# master.net
KiCad netlist of a schematic drawn in EAGLE
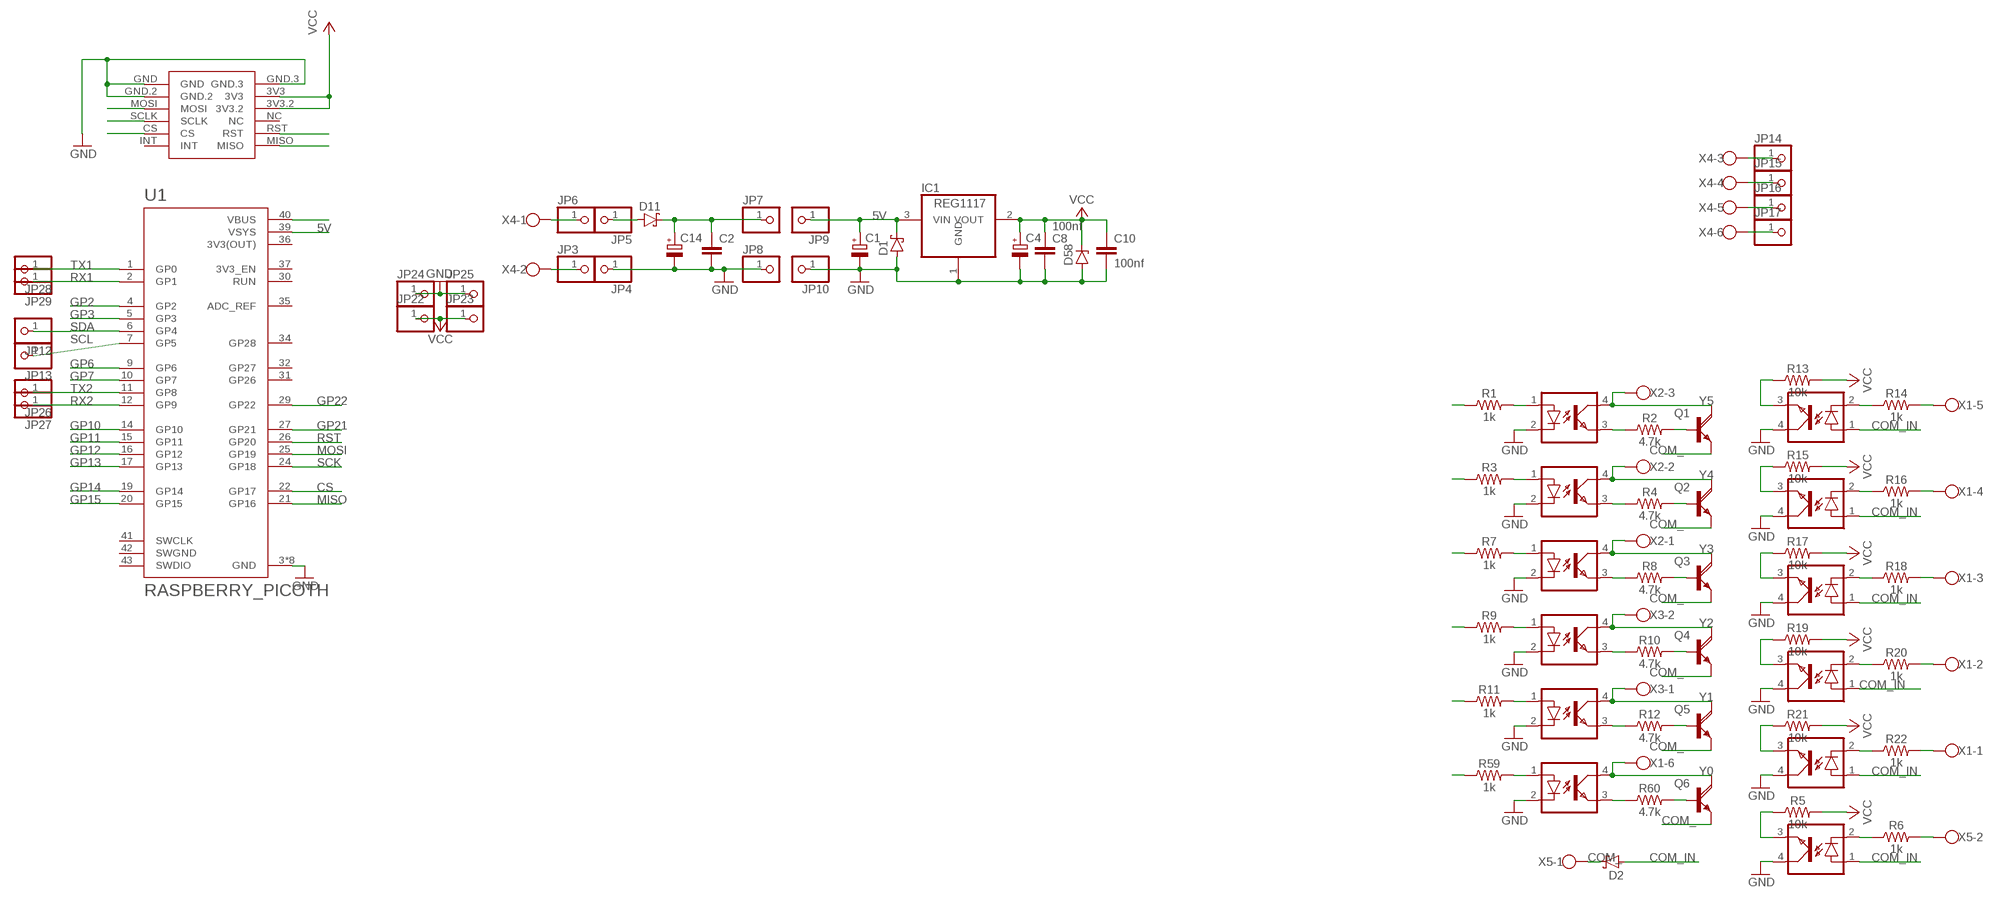
[diagram p0: schematic, sheet 1]

(export (version "E")
  (design (tool "Eeschema 10.0.6"))
  (components
    (comp (ref "C1")
      (value "CPOL-EUE2.5-7")
      (footprint "eagle-import:E2,5-7")
      (libsource (lib "eagle-import") (part "CPOL-EUE2.5-7"))
    )
    (comp (ref "C2")
      (value "C-EUC1206K")
      (footprint "eagle-import:C1206K")
      (libsource (lib "eagle-import") (part "C-EUC1206K"))
    )
    (comp (ref "C4")
      (value "CPOL-EUE2.5-7")
      (footprint "eagle-import:E2,5-7")
      (libsource (lib "eagle-import") (part "CPOL-EUE2.5-7"))
    )
    (comp (ref "C8")
      (value "100nf")
      (footprint "eagle-import:0805")
      (libsource (lib "eagle-import") (part "39NF-0805-50V-10%"))
    )
    (comp (ref "C10")
      (value "100nf")
      (footprint "eagle-import:0805")
      (libsource (lib "eagle-import") (part "39NF-0805-50V-10%"))
    )
    (comp (ref "C14")
      (value "CPOL-EUE2.5-7")
      (footprint "eagle-import:E2,5-7")
      (libsource (lib "eagle-import") (part "CPOL-EUE2.5-7"))
    )
    (comp (ref "D1")
      (value "SCHOTTKY-DIODESMD")
      (footprint "eagle-import:SMB")
      (libsource (lib "eagle-import") (part "SCHOTTKY-DIODESMD"))
    )
    (comp (ref "D2")
      (value "SCHOTTKY-DIODESMD")
      (footprint "eagle-import:SMB")
      (libsource (lib "eagle-import") (part "SCHOTTKY-DIODESMD"))
    )
    (comp (ref "D11")
      (value "SCHOTTKY-DIODESMD")
      (footprint "eagle-import:SMB")
      (libsource (lib "eagle-import") (part "SCHOTTKY-DIODESMD"))
    )
    (comp (ref "D58")
      (value "ZENER-DIODESOD80C")
      (footprint "eagle-import:SOD80C")
      (libsource (lib "eagle-import") (part "ZENER-DIODESOD80C"))
    )
    (comp (ref "IC1")
      (value "REG1117")
      (footprint "eagle-import:SOT223")
      (libsource (lib "eagle-import") (part "REG1117"))
    )
    (comp (ref "JP3")
      (value "PINHD-1X1")
      (footprint "eagle-import:1X01")
      (libsource (lib "eagle-import") (part "PINHD-1X1"))
    )
    (comp (ref "JP4")
      (value "PINHD-1X1")
      (footprint "eagle-import:1X01")
      (libsource (lib "eagle-import") (part "PINHD-1X1"))
    )
    (comp (ref "JP5")
      (value "PINHD-1X1")
      (footprint "eagle-import:1X01")
      (libsource (lib "eagle-import") (part "PINHD-1X1"))
    )
    (comp (ref "JP6")
      (value "PINHD-1X1")
      (footprint "eagle-import:1X01")
      (libsource (lib "eagle-import") (part "PINHD-1X1"))
    )
    (comp (ref "JP7")
      (value "PINHD-1X1")
      (footprint "eagle-import:1X01")
      (libsource (lib "eagle-import") (part "PINHD-1X1"))
    )
    (comp (ref "JP8")
      (value "PINHD-1X1")
      (footprint "eagle-import:1X01")
      (libsource (lib "eagle-import") (part "PINHD-1X1"))
    )
    (comp (ref "JP9")
      (value "PINHD-1X1")
      (footprint "eagle-import:1X01")
      (libsource (lib "eagle-import") (part "PINHD-1X1"))
    )
    (comp (ref "JP10")
      (value "PINHD-1X1")
      (footprint "eagle-import:1X01")
      (libsource (lib "eagle-import") (part "PINHD-1X1"))
    )
    (comp (ref "JP12")
      (value "PINHD-1X1")
      (footprint "eagle-import:1X01")
      (libsource (lib "eagle-import") (part "PINHD-1X1"))
    )
    (comp (ref "JP13")
      (value "PINHD-1X1")
      (footprint "eagle-import:1X01")
      (libsource (lib "eagle-import") (part "PINHD-1X1"))
    )
    (comp (ref "JP14")
      (value "PINHD-1X1")
      (footprint "eagle-import:1X01")
      (libsource (lib "eagle-import") (part "PINHD-1X1"))
    )
    (comp (ref "JP15")
      (value "PINHD-1X1")
      (footprint "eagle-import:1X01")
      (libsource (lib "eagle-import") (part "PINHD-1X1"))
    )
    (comp (ref "JP16")
      (value "PINHD-1X1")
      (footprint "eagle-import:1X01")
      (libsource (lib "eagle-import") (part "PINHD-1X1"))
    )
    (comp (ref "JP17")
      (value "PINHD-1X1")
      (footprint "eagle-import:1X01")
      (libsource (lib "eagle-import") (part "PINHD-1X1"))
    )
    (comp (ref "JP22")
      (value "PINHD-1X1")
      (footprint "eagle-import:1X01")
      (libsource (lib "eagle-import") (part "PINHD-1X1"))
    )
    (comp (ref "JP23")
      (value "PINHD-1X1")
      (footprint "eagle-import:1X01")
      (libsource (lib "eagle-import") (part "PINHD-1X1"))
    )
    (comp (ref "JP24")
      (value "PINHD-1X1")
      (footprint "eagle-import:1X01")
      (libsource (lib "eagle-import") (part "PINHD-1X1"))
    )
    (comp (ref "JP25")
      (value "PINHD-1X1")
      (footprint "eagle-import:1X01")
      (libsource (lib "eagle-import") (part "PINHD-1X1"))
    )
    (comp (ref "JP26")
      (value "PINHD-1X1")
      (footprint "eagle-import:1X01")
      (libsource (lib "eagle-import") (part "PINHD-1X1"))
    )
    (comp (ref "JP27")
      (value "PINHD-1X1")
      (footprint "eagle-import:1X01")
      (libsource (lib "eagle-import") (part "PINHD-1X1"))
    )
    (comp (ref "JP28")
      (value "PINHD-1X1")
      (footprint "eagle-import:1X01")
      (libsource (lib "eagle-import") (part "PINHD-1X1"))
    )
    (comp (ref "JP29")
      (value "PINHD-1X1")
      (footprint "eagle-import:1X01")
      (libsource (lib "eagle-import") (part "PINHD-1X1"))
    )
    (comp (ref "OK1")
      (value "PC817")
      (footprint "eagle-import:DIL04")
      (fields (field (name "MPN") "PC817X4J000F"))
      (libsource (lib "eagle-import") (part "PC817"))
    )
    (comp (ref "OK2")
      (value "PC817")
      (footprint "eagle-import:DIL04")
      (fields (field (name "MPN") "PC817X4J000F"))
      (libsource (lib "eagle-import") (part "PC817"))
    )
    (comp (ref "OK3")
      (value "PC817")
      (footprint "eagle-import:DIL04")
      (fields (field (name "MPN") "PC817X4J000F"))
      (libsource (lib "eagle-import") (part "PC817"))
    )
    (comp (ref "OK4")
      (value "PC817")
      (footprint "eagle-import:DIL04")
      (fields (field (name "MPN") "PC817X4J000F"))
      (libsource (lib "eagle-import") (part "PC817"))
    )
    (comp (ref "OK5")
      (value "PC817")
      (footprint "eagle-import:DIL04")
      (fields (field (name "MPN") "PC817X4J000F"))
      (libsource (lib "eagle-import") (part "PC817"))
    )
    (comp (ref "OK6")
      (value "PC817")
      (footprint "eagle-import:DIL04")
      (fields (field (name "MPN") "PC817X4J000F"))
      (libsource (lib "eagle-import") (part "PC817"))
    )
    (comp (ref "OK7")
      (value "PC817")
      (footprint "eagle-import:DIL04")
      (fields (field (name "MPN") "PC817X4J000F"))
      (libsource (lib "eagle-import") (part "PC817"))
    )
    (comp (ref "OK8")
      (value "PC817")
      (footprint "eagle-import:DIL04")
      (fields (field (name "MPN") "PC817X4J000F"))
      (libsource (lib "eagle-import") (part "PC817"))
    )
    (comp (ref "OK9")
      (value "PC817")
      (footprint "eagle-import:DIL04")
      (fields (field (name "MPN") "PC817X4J000F"))
      (libsource (lib "eagle-import") (part "PC817"))
    )
    (comp (ref "OK10")
      (value "PC817")
      (footprint "eagle-import:DIL04")
      (fields (field (name "MPN") "PC817X4J000F"))
      (libsource (lib "eagle-import") (part "PC817"))
    )
    (comp (ref "OK11")
      (value "PC817")
      (footprint "eagle-import:DIL04")
      (fields (field (name "MPN") "PC817X4J000F"))
      (libsource (lib "eagle-import") (part "PC817"))
    )
    (comp (ref "OK14")
      (value "PC817")
      (footprint "eagle-import:DIL04")
      (fields (field (name "MPN") "PC817X4J000F"))
      (libsource (lib "eagle-import") (part "PC817"))
    )
    (comp (ref "Q1")
      (value "TIP120V")
      (footprint "eagle-import:TO220AV")
      (libsource (lib "eagle-import") (part "TIP120V"))
    )
    (comp (ref "Q2")
      (value "TIP120V")
      (footprint "eagle-import:TO220AV")
      (libsource (lib "eagle-import") (part "TIP120V"))
    )
    (comp (ref "Q3")
      (value "TIP120V")
      (footprint "eagle-import:TO220AV")
      (libsource (lib "eagle-import") (part "TIP120V"))
    )
    (comp (ref "Q4")
      (value "TIP120V")
      (footprint "eagle-import:TO220AV")
      (libsource (lib "eagle-import") (part "TIP120V"))
    )
    (comp (ref "Q5")
      (value "TIP120V")
      (footprint "eagle-import:TO220AV")
      (libsource (lib "eagle-import") (part "TIP120V"))
    )
    (comp (ref "Q6")
      (value "TIP120V")
      (footprint "eagle-import:TO220AV")
      (libsource (lib "eagle-import") (part "TIP120V"))
    )
    (comp (ref "R1")
      (value "1k")
      (footprint "eagle-import:0805")
      (libsource (lib "eagle-import") (part "0.75OHM-0805-1/4W-1%"))
    )
    (comp (ref "R2")
      (value "4.7k")
      (footprint "eagle-import:0805")
      (libsource (lib "eagle-import") (part "0.75OHM-0805-1/4W-1%"))
    )
    (comp (ref "R3")
      (value "1k")
      (footprint "eagle-import:0805")
      (libsource (lib "eagle-import") (part "0.75OHM-0805-1/4W-1%"))
    )
    (comp (ref "R4")
      (value "4.7k")
      (footprint "eagle-import:0805")
      (libsource (lib "eagle-import") (part "0.75OHM-0805-1/4W-1%"))
    )
    (comp (ref "R5")
      (value "10k")
      (footprint "eagle-import:0805")
      (libsource (lib "eagle-import") (part "0.75OHM-0805-1/4W-1%"))
    )
    (comp (ref "R6")
      (value "1k")
      (footprint "eagle-import:0805")
      (libsource (lib "eagle-import") (part "0.75OHM-0805-1/4W-1%"))
    )
    (comp (ref "R7")
      (value "1k")
      (footprint "eagle-import:0805")
      (libsource (lib "eagle-import") (part "0.75OHM-0805-1/4W-1%"))
    )
    (comp (ref "R8")
      (value "4.7k")
      (footprint "eagle-import:0805")
      (libsource (lib "eagle-import") (part "0.75OHM-0805-1/4W-1%"))
    )
    (comp (ref "R9")
      (value "1k")
      (footprint "eagle-import:0805")
      (libsource (lib "eagle-import") (part "0.75OHM-0805-1/4W-1%"))
    )
    (comp (ref "R10")
      (value "4.7k")
      (footprint "eagle-import:0805")
      (libsource (lib "eagle-import") (part "0.75OHM-0805-1/4W-1%"))
    )
    (comp (ref "R11")
      (value "1k")
      (footprint "eagle-import:0805")
      (libsource (lib "eagle-import") (part "0.75OHM-0805-1/4W-1%"))
    )
    (comp (ref "R12")
      (value "4.7k")
      (footprint "eagle-import:0805")
      (libsource (lib "eagle-import") (part "0.75OHM-0805-1/4W-1%"))
    )
    (comp (ref "R13")
      (value "10k")
      (footprint "eagle-import:0805")
      (libsource (lib "eagle-import") (part "0.75OHM-0805-1/4W-1%"))
    )
    (comp (ref "R14")
      (value "1k")
      (footprint "eagle-import:0805")
      (libsource (lib "eagle-import") (part "0.75OHM-0805-1/4W-1%"))
    )
    (comp (ref "R15")
      (value "10k")
      (footprint "eagle-import:0805")
      (libsource (lib "eagle-import") (part "0.75OHM-0805-1/4W-1%"))
    )
    (comp (ref "R16")
      (value "1k")
      (footprint "eagle-import:0805")
      (libsource (lib "eagle-import") (part "0.75OHM-0805-1/4W-1%"))
    )
    (comp (ref "R17")
      (value "10k")
      (footprint "eagle-import:0805")
      (libsource (lib "eagle-import") (part "0.75OHM-0805-1/4W-1%"))
    )
    (comp (ref "R18")
      (value "1k")
      (footprint "eagle-import:0805")
      (libsource (lib "eagle-import") (part "0.75OHM-0805-1/4W-1%"))
    )
    (comp (ref "R19")
      (value "10k")
      (footprint "eagle-import:0805")
      (libsource (lib "eagle-import") (part "0.75OHM-0805-1/4W-1%"))
    )
    (comp (ref "R20")
      (value "1k")
      (footprint "eagle-import:0805")
      (libsource (lib "eagle-import") (part "0.75OHM-0805-1/4W-1%"))
    )
    (comp (ref "R21")
      (value "10k")
      (footprint "eagle-import:0805")
      (libsource (lib "eagle-import") (part "0.75OHM-0805-1/4W-1%"))
    )
    (comp (ref "R22")
      (value "1k")
      (footprint "eagle-import:0805")
      (libsource (lib "eagle-import") (part "0.75OHM-0805-1/4W-1%"))
    )
    (comp (ref "R59")
      (value "1k")
      (footprint "eagle-import:0805")
      (libsource (lib "eagle-import") (part "0.75OHM-0805-1/4W-1%"))
    )
    (comp (ref "R60")
      (value "4.7k")
      (footprint "eagle-import:0805")
      (libsource (lib "eagle-import") (part "0.75OHM-0805-1/4W-1%"))
    )
    (comp (ref "U$2")
      (value "MINI_W5500")
      (footprint "eagle-import:MINI_W5500")
      (libsource (lib "eagle-import") (part "MINI_W5500"))
    )
    (comp (ref "U1")
      (value "RASPBERRY_PICOTH")
      (footprint "eagle-import:PICO-PKG-TH")
      (libsource (lib "eagle-import") (part "RASPBERRY_PICOTH"))
    )
    (comp (ref "X1")
      (value "W237-136")
      (footprint "eagle-import:W237-136")
      (fields (field (name "MPN") "237-136"))
      (libsource (lib "eagle-import") (part "W237-136"))
    )
    (comp (ref "X2")
      (value "W237-103")
      (footprint "eagle-import:W237-103")
      (fields (field (name "MPN") "237-103"))
      (libsource (lib "eagle-import") (part "W237-103"))
    )
    (comp (ref "X3")
      (value "W237-102")
      (footprint "eagle-import:W237-102")
      (fields (field (name "MPN") "237-102"))
      (libsource (lib "eagle-import") (part "W237-102"))
    )
    (comp (ref "X4")
      (value "W237-136")
      (footprint "eagle-import:W237-136")
      (fields (field (name "MPN") "237-136"))
      (libsource (lib "eagle-import") (part "W237-136"))
    )
    (comp (ref "X5")
      (value "W237-102")
      (footprint "eagle-import:W237-102")
      (fields (field (name "MPN") "237-102"))
      (libsource (lib "eagle-import") (part "W237-102"))
    )
  )
  (nets
    (net (code "1") (name "/3V3(OUT)") (class "Default")
      (node (ref "U1") (pin "36") (pinfunction "3V3(OUT)_36") (pintype "power_in"))
    )
    (net (code "2") (name "/5V") (class "Default")
      (node (ref "C1") (pin "+") (pinfunction "+_+") (pintype "passive"))
      (node (ref "D1") (pin "C") (pinfunction "C_C") (pintype "passive"))
      (node (ref "IC1") (pin "3") (pinfunction "VIN_3") (pintype "input"))
      (node (ref "JP9") (pin "1") (pinfunction "1_1") (pintype "passive"))
      (node (ref "U1") (pin "39") (pinfunction "VSYS_39") (pintype "power_in"))
    )
    (net (code "3") (name "/COM_") (class "Default")
      (node (ref "D2") (pin "C") (pinfunction "C_C") (pintype "passive"))
      (node (ref "Q1") (pin "E") (pinfunction "E_E") (pintype "passive"))
      (node (ref "Q2") (pin "E") (pinfunction "E_E") (pintype "passive"))
      (node (ref "Q3") (pin "E") (pinfunction "E_E") (pintype "passive"))
      (node (ref "Q4") (pin "E") (pinfunction "E_E") (pintype "passive"))
      (node (ref "Q5") (pin "E") (pinfunction "E_E") (pintype "passive"))
      (node (ref "Q6") (pin "E") (pinfunction "E_E") (pintype "passive"))
      (node (ref "X5") (pin "1") (pinfunction "KL_1") (pintype "passive"))
    )
    (net (code "4") (name "/COM_IN") (class "Default")
      (node (ref "D2") (pin "A") (pinfunction "A_A") (pintype "passive"))
      (node (ref "OK10") (pin "1") (pinfunction "A_1") (pintype "passive"))
      (node (ref "OK11") (pin "1") (pinfunction "A_1") (pintype "passive"))
      (node (ref "OK3") (pin "1") (pinfunction "A_1") (pintype "passive"))
      (node (ref "OK7") (pin "1") (pinfunction "A_1") (pintype "passive"))
      (node (ref "OK8") (pin "1") (pinfunction "A_1") (pintype "passive"))
      (node (ref "OK9") (pin "1") (pinfunction "A_1") (pintype "passive"))
    )
    (net (code "5") (name "/CS") (class "Default")
      (node (ref "U1") (pin "22") (pinfunction "GP17_22") (pintype "bidirectional"))
    )
    (net (code "6") (name "/GP2") (class "Default")
      (node (ref "U1") (pin "4") (pinfunction "GP2_4") (pintype "bidirectional"))
    )
    (net (code "7") (name "/GP3") (class "Default")
      (node (ref "U1") (pin "5") (pinfunction "GP3_5") (pintype "bidirectional"))
    )
    (net (code "8") (name "/GP6") (class "Default")
      (node (ref "U1") (pin "9") (pinfunction "GP6_9") (pintype "bidirectional"))
    )
    (net (code "9") (name "/GP7") (class "Default")
      (node (ref "U1") (pin "10") (pinfunction "GP7_10") (pintype "bidirectional"))
    )
    (net (code "10") (name "/GP10") (class "Default")
      (node (ref "U1") (pin "14") (pinfunction "GP10_14") (pintype "bidirectional"))
    )
    (net (code "11") (name "/GP11") (class "Default")
      (node (ref "U1") (pin "15") (pinfunction "GP11_15") (pintype "bidirectional"))
    )
    (net (code "12") (name "/GP12") (class "Default")
      (node (ref "U1") (pin "16") (pinfunction "GP12_16") (pintype "bidirectional"))
    )
    (net (code "13") (name "/GP13") (class "Default")
      (node (ref "U1") (pin "17") (pinfunction "GP13_17") (pintype "bidirectional"))
    )
    (net (code "14") (name "/GP14") (class "Default")
      (node (ref "U1") (pin "19") (pinfunction "GP14_19") (pintype "bidirectional"))
    )
    (net (code "15") (name "/GP15") (class "Default")
      (node (ref "U1") (pin "20") (pinfunction "GP15_20") (pintype "bidirectional"))
    )
    (net (code "16") (name "/GP21") (class "Default")
      (node (ref "U1") (pin "27") (pinfunction "GP21_27") (pintype "bidirectional"))
    )
    (net (code "17") (name "/GP22") (class "Default")
      (node (ref "U1") (pin "29") (pinfunction "GP22_29") (pintype "bidirectional"))
    )
    (net (code "18") (name "/MISO") (class "Default")
      (node (ref "U1") (pin "21") (pinfunction "GP16_21") (pintype "bidirectional"))
    )
    (net (code "19") (name "/MOSI") (class "Default")
      (node (ref "U1") (pin "25") (pinfunction "GP19_25") (pintype "bidirectional"))
    )
    (net (code "20") (name "/RST") (class "Default")
      (node (ref "U1") (pin "26") (pinfunction "GP20_26") (pintype "bidirectional"))
    )
    (net (code "21") (name "/RX1") (class "Default")
      (node (ref "JP29") (pin "1") (pinfunction "1_1") (pintype "passive"))
      (node (ref "U1") (pin "2") (pinfunction "GP1_2") (pintype "bidirectional"))
    )
    (net (code "22") (name "/RX2") (class "Default")
      (node (ref "JP27") (pin "1") (pinfunction "1_1") (pintype "passive"))
      (node (ref "U1") (pin "12") (pinfunction "GP9_12") (pintype "bidirectional"))
    )
    (net (code "23") (name "/SCK") (class "Default")
      (node (ref "U1") (pin "24") (pinfunction "GP18_24") (pintype "bidirectional"))
    )
    (net (code "24") (name "/SCL") (class "Default")
      (node (ref "JP13") (pin "1") (pinfunction "1_1") (pintype "passive"))
      (node (ref "U1") (pin "7") (pinfunction "GP5_7") (pintype "bidirectional"))
    )
    (net (code "25") (name "/SDA") (class "Default")
      (node (ref "JP12") (pin "1") (pinfunction "1_1") (pintype "passive"))
      (node (ref "U1") (pin "6") (pinfunction "GP4_6") (pintype "bidirectional"))
    )
    (net (code "26") (name "/SWGND") (class "Default")
      (node (ref "U1") (pin "42") (pinfunction "SWGND_42") (pintype "power_in"))
    )
    (net (code "27") (name "/TX1") (class "Default")
      (node (ref "JP28") (pin "1") (pinfunction "1_1") (pintype "passive"))
      (node (ref "U1") (pin "1") (pinfunction "GP0_1") (pintype "bidirectional"))
    )
    (net (code "28") (name "/TX2") (class "Default")
      (node (ref "JP26") (pin "1") (pinfunction "1_1") (pintype "passive"))
      (node (ref "U1") (pin "11") (pinfunction "GP8_11") (pintype "bidirectional"))
    )
    (net (code "29") (name "/Y0") (class "Default")
      (node (ref "OK14") (pin "4") (pinfunction "COL_4") (pintype "passive"))
      (node (ref "Q6") (pin "C") (pinfunction "C_C") (pintype "passive"))
      (node (ref "X1") (pin "6") (pinfunction "KL_6") (pintype "passive"))
    )
    (net (code "30") (name "/Y1") (class "Default")
      (node (ref "OK6") (pin "4") (pinfunction "COL_4") (pintype "passive"))
      (node (ref "Q5") (pin "C") (pinfunction "C_C") (pintype "passive"))
      (node (ref "X3") (pin "1") (pinfunction "KL_1") (pintype "passive"))
    )
    (net (code "31") (name "/Y2") (class "Default")
      (node (ref "OK5") (pin "4") (pinfunction "COL_4") (pintype "passive"))
      (node (ref "Q4") (pin "C") (pinfunction "C_C") (pintype "passive"))
      (node (ref "X3") (pin "2") (pinfunction "KL_2") (pintype "passive"))
    )
    (net (code "32") (name "/Y3") (class "Default")
      (node (ref "OK4") (pin "4") (pinfunction "COL_4") (pintype "passive"))
      (node (ref "Q3") (pin "C") (pinfunction "C_C") (pintype "passive"))
      (node (ref "X2") (pin "1") (pinfunction "KL_1") (pintype "passive"))
    )
    (net (code "33") (name "/Y4") (class "Default")
      (node (ref "OK2") (pin "4") (pinfunction "COL_4") (pintype "passive"))
      (node (ref "Q2") (pin "C") (pinfunction "C_C") (pintype "passive"))
      (node (ref "X2") (pin "2") (pinfunction "KL_2") (pintype "passive"))
    )
    (net (code "34") (name "/Y5") (class "Default")
      (node (ref "OK1") (pin "4") (pinfunction "COL_4") (pintype "passive"))
      (node (ref "Q1") (pin "C") (pinfunction "C_C") (pintype "passive"))
      (node (ref "X2") (pin "3") (pinfunction "KL_3") (pintype "passive"))
    )
    (net (code "35") (name "GND") (class "Default")
      (node (ref "C1") (pin "-") (pinfunction "-_-") (pintype "passive"))
      (node (ref "C10") (pin "2") (pinfunction "2_2") (pintype "passive"))
      (node (ref "C14") (pin "-") (pinfunction "-_-") (pintype "passive"))
      (node (ref "C2") (pin "2") (pinfunction "2_2") (pintype "passive"))
      (node (ref "C4") (pin "-") (pinfunction "-_-") (pintype "passive"))
      (node (ref "C8") (pin "2") (pinfunction "2_2") (pintype "passive"))
      (node (ref "D1") (pin "A") (pinfunction "A_A") (pintype "passive"))
      (node (ref "D58") (pin "A") (pinfunction "A_A") (pintype "passive"))
      (node (ref "IC1") (pin "1") (pinfunction "GND_1") (pintype "power_in"))
      (node (ref "JP10") (pin "1") (pinfunction "1_1") (pintype "passive"))
      (node (ref "JP24") (pin "1") (pinfunction "1_1") (pintype "passive"))
      (node (ref "JP25") (pin "1") (pinfunction "1_1") (pintype "passive"))
      (node (ref "JP4") (pin "1") (pinfunction "1_1") (pintype "passive"))
      (node (ref "JP8") (pin "1") (pinfunction "1_1") (pintype "passive"))
      (node (ref "OK1") (pin "2") (pinfunction "C_2") (pintype "passive"))
      (node (ref "OK10") (pin "4") (pinfunction "COL_4") (pintype "passive"))
      (node (ref "OK11") (pin "4") (pinfunction "COL_4") (pintype "passive"))
      (node (ref "OK14") (pin "2") (pinfunction "C_2") (pintype "passive"))
      (node (ref "OK2") (pin "2") (pinfunction "C_2") (pintype "passive"))
      (node (ref "OK3") (pin "4") (pinfunction "COL_4") (pintype "passive"))
      (node (ref "OK4") (pin "2") (pinfunction "C_2") (pintype "passive"))
      (node (ref "OK5") (pin "2") (pinfunction "C_2") (pintype "passive"))
      (node (ref "OK6") (pin "2") (pinfunction "C_2") (pintype "passive"))
      (node (ref "OK7") (pin "4") (pinfunction "COL_4") (pintype "passive"))
      (node (ref "OK8") (pin "4") (pinfunction "COL_4") (pintype "passive"))
      (node (ref "OK9") (pin "4") (pinfunction "COL_4") (pintype "passive"))
      (node (ref "U$2") (pin "GND") (pinfunction "GND_GND") (pintype "bidirectional"))
      (node (ref "U$2") (pin "GND.2") (pinfunction "GND.2_GND.2") (pintype "bidirectional"))
      (node (ref "U$2") (pin "GND.3") (pinfunction "GND.3_GND.3") (pintype "bidirectional"))
      (node (ref "U1") (pin "13") (pinfunction "GND_13") (pintype "power_in"))
      (node (ref "U1") (pin "18") (pinfunction "GND_18") (pintype "power_in"))
      (node (ref "U1") (pin "23") (pinfunction "GND_23") (pintype "power_in"))
      (node (ref "U1") (pin "28") (pinfunction "GND_28") (pintype "power_in"))
      (node (ref "U1") (pin "3") (pinfunction "GND_3") (pintype "power_in"))
      (node (ref "U1") (pin "33") (pinfunction "GND_33") (pintype "power_in"))
      (node (ref "U1") (pin "38") (pinfunction "GND_38") (pintype "power_in"))
      (node (ref "U1") (pin "8") (pinfunction "GND_8") (pintype "power_in"))
    )
    (net (code "36") (name "Net-(C14-Pad+)") (class "Default")
      (node (ref "C14") (pin "+") (pinfunction "+_+") (pintype "passive"))
      (node (ref "C2") (pin "1") (pinfunction "1_1") (pintype "passive"))
      (node (ref "D11") (pin "C") (pinfunction "C_C") (pintype "passive"))
      (node (ref "JP7") (pin "1") (pinfunction "1_1") (pintype "passive"))
    )
    (net (code "37") (name "Net-(D11-PadA)") (class "Default")
      (node (ref "D11") (pin "A") (pinfunction "A_A") (pintype "passive"))
      (node (ref "JP5") (pin "1") (pinfunction "1_1") (pintype "passive"))
    )
    (net (code "38") (name "Net-(OK1-A)") (class "Default")
      (node (ref "OK1") (pin "1") (pinfunction "A_1") (pintype "passive"))
      (node (ref "R1") (pin "2") (pinfunction "2_2") (pintype "passive"))
    )
    (net (code "39") (name "Net-(OK1-EMIT)") (class "Default")
      (node (ref "OK1") (pin "3") (pinfunction "EMIT_3") (pintype "passive"))
      (node (ref "R2") (pin "1") (pinfunction "1_1") (pintype "passive"))
    )
    (net (code "40") (name "Net-(OK2-A)") (class "Default")
      (node (ref "OK2") (pin "1") (pinfunction "A_1") (pintype "passive"))
      (node (ref "R3") (pin "2") (pinfunction "2_2") (pintype "passive"))
    )
    (net (code "41") (name "Net-(OK2-EMIT)") (class "Default")
      (node (ref "OK2") (pin "3") (pinfunction "EMIT_3") (pintype "passive"))
      (node (ref "R4") (pin "1") (pinfunction "1_1") (pintype "passive"))
    )
    (net (code "42") (name "Net-(OK3-C)") (class "Default")
      (node (ref "OK3") (pin "2") (pinfunction "C_2") (pintype "passive"))
      (node (ref "R6") (pin "1") (pinfunction "1_1") (pintype "passive"))
    )
    (net (code "43") (name "Net-(OK3-EMIT)") (class "Default")
      (node (ref "OK3") (pin "3") (pinfunction "EMIT_3") (pintype "passive"))
      (node (ref "R5") (pin "1") (pinfunction "1_1") (pintype "passive"))
    )
    (net (code "44") (name "Net-(OK4-A)") (class "Default")
      (node (ref "OK4") (pin "1") (pinfunction "A_1") (pintype "passive"))
      (node (ref "R7") (pin "2") (pinfunction "2_2") (pintype "passive"))
    )
    (net (code "45") (name "Net-(OK4-EMIT)") (class "Default")
      (node (ref "OK4") (pin "3") (pinfunction "EMIT_3") (pintype "passive"))
      (node (ref "R8") (pin "1") (pinfunction "1_1") (pintype "passive"))
    )
    (net (code "46") (name "Net-(OK5-A)") (class "Default")
      (node (ref "OK5") (pin "1") (pinfunction "A_1") (pintype "passive"))
      (node (ref "R9") (pin "2") (pinfunction "2_2") (pintype "passive"))
    )
    (net (code "47") (name "Net-(OK5-EMIT)") (class "Default")
      (node (ref "OK5") (pin "3") (pinfunction "EMIT_3") (pintype "passive"))
      (node (ref "R10") (pin "1") (pinfunction "1_1") (pintype "passive"))
    )
    (net (code "48") (name "Net-(OK6-A)") (class "Default")
      (node (ref "OK6") (pin "1") (pinfunction "A_1") (pintype "passive"))
      (node (ref "R11") (pin "2") (pinfunction "2_2") (pintype "passive"))
    )
    (net (code "49") (name "Net-(OK6-EMIT)") (class "Default")
      (node (ref "OK6") (pin "3") (pinfunction "EMIT_3") (pintype "passive"))
      (node (ref "R12") (pin "1") (pinfunction "1_1") (pintype "passive"))
    )
    (net (code "50") (name "Net-(OK7-C)") (class "Default")
      (node (ref "OK7") (pin "2") (pinfunction "C_2") (pintype "passive"))
      (node (ref "R14") (pin "1") (pinfunction "1_1") (pintype "passive"))
    )
    (net (code "51") (name "Net-(OK7-EMIT)") (class "Default")
      (node (ref "OK7") (pin "3") (pinfunction "EMIT_3") (pintype "passive"))
      (node (ref "R13") (pin "1") (pinfunction "1_1") (pintype "passive"))
    )
    (net (code "52") (name "Net-(OK8-C)") (class "Default")
      (node (ref "OK8") (pin "2") (pinfunction "C_2") (pintype "passive"))
      (node (ref "R16") (pin "1") (pinfunction "1_1") (pintype "passive"))
    )
    (net (code "53") (name "Net-(OK8-EMIT)") (class "Default")
      (node (ref "OK8") (pin "3") (pinfunction "EMIT_3") (pintype "passive"))
      (node (ref "R15") (pin "1") (pinfunction "1_1") (pintype "passive"))
    )
    (net (code "54") (name "Net-(OK9-C)") (class "Default")
      (node (ref "OK9") (pin "2") (pinfunction "C_2") (pintype "passive"))
      (node (ref "R18") (pin "1") (pinfunction "1_1") (pintype "passive"))
    )
    (net (code "55") (name "Net-(OK9-EMIT)") (class "Default")
      (node (ref "OK9") (pin "3") (pinfunction "EMIT_3") (pintype "passive"))
      (node (ref "R17") (pin "1") (pinfunction "1_1") (pintype "passive"))
    )
    (net (code "56") (name "Net-(OK10-C)") (class "Default")
      (node (ref "OK10") (pin "2") (pinfunction "C_2") (pintype "passive"))
      (node (ref "R20") (pin "1") (pinfunction "1_1") (pintype "passive"))
    )
    (net (code "57") (name "Net-(OK10-EMIT)") (class "Default")
      (node (ref "OK10") (pin "3") (pinfunction "EMIT_3") (pintype "passive"))
      (node (ref "R19") (pin "1") (pinfunction "1_1") (pintype "passive"))
    )
    (net (code "58") (name "Net-(OK11-C)") (class "Default")
      (node (ref "OK11") (pin "2") (pinfunction "C_2") (pintype "passive"))
      (node (ref "R22") (pin "1") (pinfunction "1_1") (pintype "passive"))
    )
    (net (code "59") (name "Net-(OK11-EMIT)") (class "Default")
      (node (ref "OK11") (pin "3") (pinfunction "EMIT_3") (pintype "passive"))
      (node (ref "R21") (pin "1") (pinfunction "1_1") (pintype "passive"))
    )
    (net (code "60") (name "Net-(OK14-A)") (class "Default")
      (node (ref "OK14") (pin "1") (pinfunction "A_1") (pintype "passive"))
      (node (ref "R59") (pin "2") (pinfunction "2_2") (pintype "passive"))
    )
    (net (code "61") (name "Net-(OK14-EMIT)") (class "Default")
      (node (ref "OK14") (pin "3") (pinfunction "EMIT_3") (pintype "passive"))
      (node (ref "R60") (pin "1") (pinfunction "1_1") (pintype "passive"))
    )
    (net (code "62") (name "Net-(Q1-PadB)") (class "Default")
      (node (ref "Q1") (pin "B") (pinfunction "B_B") (pintype "passive"))
      (node (ref "R2") (pin "2") (pinfunction "2_2") (pintype "passive"))
    )
    (net (code "63") (name "Net-(Q2-PadB)") (class "Default")
      (node (ref "Q2") (pin "B") (pinfunction "B_B") (pintype "passive"))
      (node (ref "R4") (pin "2") (pinfunction "2_2") (pintype "passive"))
    )
    (net (code "64") (name "Net-(Q3-PadB)") (class "Default")
      (node (ref "Q3") (pin "B") (pinfunction "B_B") (pintype "passive"))
      (node (ref "R8") (pin "2") (pinfunction "2_2") (pintype "passive"))
    )
    (net (code "65") (name "Net-(Q4-PadB)") (class "Default")
      (node (ref "Q4") (pin "B") (pinfunction "B_B") (pintype "passive"))
      (node (ref "R10") (pin "2") (pinfunction "2_2") (pintype "passive"))
    )
    (net (code "66") (name "Net-(Q5-PadB)") (class "Default")
      (node (ref "Q5") (pin "B") (pinfunction "B_B") (pintype "passive"))
      (node (ref "R12") (pin "2") (pinfunction "2_2") (pintype "passive"))
    )
    (net (code "67") (name "Net-(Q6-PadB)") (class "Default")
      (node (ref "Q6") (pin "B") (pinfunction "B_B") (pintype "passive"))
      (node (ref "R60") (pin "2") (pinfunction "2_2") (pintype "passive"))
    )
    (net (code "68") (name "Net-(X1A-KL)") (class "Default")
      (node (ref "R22") (pin "2") (pinfunction "2_2") (pintype "passive"))
      (node (ref "X1") (pin "1") (pinfunction "KL_1") (pintype "passive"))
    )
    (net (code "69") (name "Net-(X1B-KL)") (class "Default")
      (node (ref "R20") (pin "2") (pinfunction "2_2") (pintype "passive"))
      (node (ref "X1") (pin "2") (pinfunction "KL_2") (pintype "passive"))
    )
    (net (code "70") (name "Net-(X1C-KL)") (class "Default")
      (node (ref "R18") (pin "2") (pinfunction "2_2") (pintype "passive"))
      (node (ref "X1") (pin "3") (pinfunction "KL_3") (pintype "passive"))
    )
    (net (code "71") (name "Net-(X1D-KL)") (class "Default")
      (node (ref "R16") (pin "2") (pinfunction "2_2") (pintype "passive"))
      (node (ref "X1") (pin "4") (pinfunction "KL_4") (pintype "passive"))
    )
    (net (code "72") (name "Net-(X1E-KL)") (class "Default")
      (node (ref "R14") (pin "2") (pinfunction "2_2") (pintype "passive"))
      (node (ref "X1") (pin "5") (pinfunction "KL_5") (pintype "passive"))
    )
    (net (code "73") (name "Net-(X4A-KL)") (class "Default")
      (node (ref "JP6") (pin "1") (pinfunction "1_1") (pintype "passive"))
      (node (ref "X4") (pin "1") (pinfunction "KL_1") (pintype "passive"))
    )
    (net (code "74") (name "Net-(X4B-KL)") (class "Default")
      (node (ref "JP3") (pin "1") (pinfunction "1_1") (pintype "passive"))
      (node (ref "X4") (pin "2") (pinfunction "KL_2") (pintype "passive"))
    )
    (net (code "75") (name "Net-(X4C-KL)") (class "Default")
      (node (ref "JP14") (pin "1") (pinfunction "1_1") (pintype "passive"))
      (node (ref "X4") (pin "3") (pinfunction "KL_3") (pintype "passive"))
    )
    (net (code "76") (name "Net-(X4D-KL)") (class "Default")
      (node (ref "JP15") (pin "1") (pinfunction "1_1") (pintype "passive"))
      (node (ref "X4") (pin "4") (pinfunction "KL_4") (pintype "passive"))
    )
    (net (code "77") (name "Net-(X4E-KL)") (class "Default")
      (node (ref "JP16") (pin "1") (pinfunction "1_1") (pintype "passive"))
      (node (ref "X4") (pin "5") (pinfunction "KL_5") (pintype "passive"))
    )
    (net (code "78") (name "Net-(X4F-KL)") (class "Default")
      (node (ref "JP17") (pin "1") (pinfunction "1_1") (pintype "passive"))
      (node (ref "X4") (pin "6") (pinfunction "KL_6") (pintype "passive"))
    )
    (net (code "79") (name "Net-(X5B-KL)") (class "Default")
      (node (ref "R6") (pin "2") (pinfunction "2_2") (pintype "passive"))
      (node (ref "X5") (pin "2") (pinfunction "KL_2") (pintype "passive"))
    )
    (net (code "80") (name "VCC") (class "Default")
      (node (ref "C10") (pin "1") (pinfunction "1_1") (pintype "passive"))
      (node (ref "C4") (pin "+") (pinfunction "+_+") (pintype "passive"))
      (node (ref "C8") (pin "1") (pinfunction "1_1") (pintype "passive"))
      (node (ref "D58") (pin "C") (pinfunction "C_C") (pintype "passive"))
      (node (ref "IC1") (pin "2") (pinfunction "VOUT_2") (pintype "output"))
      (node (ref "JP22") (pin "1") (pinfunction "1_1") (pintype "passive"))
      (node (ref "JP23") (pin "1") (pinfunction "1_1") (pintype "passive"))
      (node (ref "R13") (pin "2") (pinfunction "2_2") (pintype "passive"))
      (node (ref "R15") (pin "2") (pinfunction "2_2") (pintype "passive"))
      (node (ref "R17") (pin "2") (pinfunction "2_2") (pintype "passive"))
      (node (ref "R19") (pin "2") (pinfunction "2_2") (pintype "passive"))
      (node (ref "R21") (pin "2") (pinfunction "2_2") (pintype "passive"))
      (node (ref "R5") (pin "2") (pinfunction "2_2") (pintype "passive"))
      (node (ref "U$2") (pin "3V3") (pinfunction "3V3_3V3") (pintype "bidirectional"))
      (node (ref "U$2") (pin "3V3.2") (pinfunction "3V3.2_3V3.2") (pintype "bidirectional"))
    )
    (net (code "81") (name "unconnected-(R1-Pad1)") (class "Default")
      (node (ref "R1") (pin "1") (pinfunction "1_1") (pintype "passive"))
    )
    (net (code "82") (name "unconnected-(R3-Pad1)") (class "Default")
      (node (ref "R3") (pin "1") (pinfunction "1_1") (pintype "passive"))
    )
    (net (code "83") (name "unconnected-(R7-Pad1)") (class "Default")
      (node (ref "R7") (pin "1") (pinfunction "1_1") (pintype "passive"))
    )
    (net (code "84") (name "unconnected-(R9-Pad1)") (class "Default")
      (node (ref "R9") (pin "1") (pinfunction "1_1") (pintype "passive"))
    )
    (net (code "85") (name "unconnected-(R11-Pad1)") (class "Default")
      (node (ref "R11") (pin "1") (pinfunction "1_1") (pintype "passive"))
    )
    (net (code "86") (name "unconnected-(R59-Pad1)") (class "Default")
      (node (ref "R59") (pin "1") (pinfunction "1_1") (pintype "passive"))
    )
    (net (code "87") (name "unconnected-(U$2-PadCS)") (class "Default")
      (node (ref "U$2") (pin "CS") (pinfunction "CS_CS") (pintype "bidirectional"))
    )
    (net (code "88") (name "unconnected-(U$2-PadINT)") (class "Default")
      (node (ref "U$2") (pin "INT") (pinfunction "INT_INT") (pintype "bidirectional"))
    )
    (net (code "89") (name "unconnected-(U$2-PadMISO)") (class "Default")
      (node (ref "U$2") (pin "MISO") (pinfunction "MISO_MISO") (pintype "bidirectional"))
    )
    (net (code "90") (name "unconnected-(U$2-PadMOSI)") (class "Default")
      (node (ref "U$2") (pin "MOSI") (pinfunction "MOSI_MOSI") (pintype "bidirectional"))
    )
    (net (code "91") (name "unconnected-(U$2-PadNC)") (class "Default")
      (node (ref "U$2") (pin "NC") (pinfunction "NC_NC") (pintype "bidirectional"))
    )
    (net (code "92") (name "unconnected-(U$2-PadRST)") (class "Default")
      (node (ref "U$2") (pin "RST") (pinfunction "RST_RST") (pintype "bidirectional"))
    )
    (net (code "93") (name "unconnected-(U$2-PadSCLK)") (class "Default")
      (node (ref "U$2") (pin "SCLK") (pinfunction "SCLK_SCLK") (pintype "bidirectional"))
    )
    (net (code "94") (name "unconnected-(U1-3V3_EN-Pad37)") (class "Default")
      (node (ref "U1") (pin "37") (pinfunction "3V3_EN_37") (pintype "input"))
    )
    (net (code "95") (name "unconnected-(U1-ADC_REF-Pad35)") (class "Default")
      (node (ref "U1") (pin "35") (pinfunction "ADC_REF_35") (pintype "input"))
    )
    (net (code "96") (name "unconnected-(U1-GP26-Pad31)") (class "Default")
      (node (ref "U1") (pin "31") (pinfunction "GP26_31") (pintype "bidirectional"))
    )
    (net (code "97") (name "unconnected-(U1-GP27-Pad32)") (class "Default")
      (node (ref "U1") (pin "32") (pinfunction "GP27_32") (pintype "bidirectional"))
    )
    (net (code "98") (name "unconnected-(U1-GP28-Pad34)") (class "Default")
      (node (ref "U1") (pin "34") (pinfunction "GP28_34") (pintype "bidirectional"))
    )
    (net (code "99") (name "unconnected-(U1-RUN-Pad30)") (class "Default")
      (node (ref "U1") (pin "30") (pinfunction "RUN_30") (pintype "input"))
    )
    (net (code "100") (name "unconnected-(U1-SWCLK-Pad41)") (class "Default")
      (node (ref "U1") (pin "41") (pinfunction "SWCLK_41") (pintype "input"))
    )
    (net (code "101") (name "unconnected-(U1-SWDIO-Pad43)") (class "Default")
      (node (ref "U1") (pin "43") (pinfunction "SWDIO_43") (pintype "bidirectional"))
    )
    (net (code "102") (name "unconnected-(U1-VBUS-Pad40)") (class "Default")
      (node (ref "U1") (pin "40") (pinfunction "VBUS_40") (pintype "power_in"))
    )
  )
)
